# sunclock.net
KiCad netlist of a schematic drawn in EAGLE
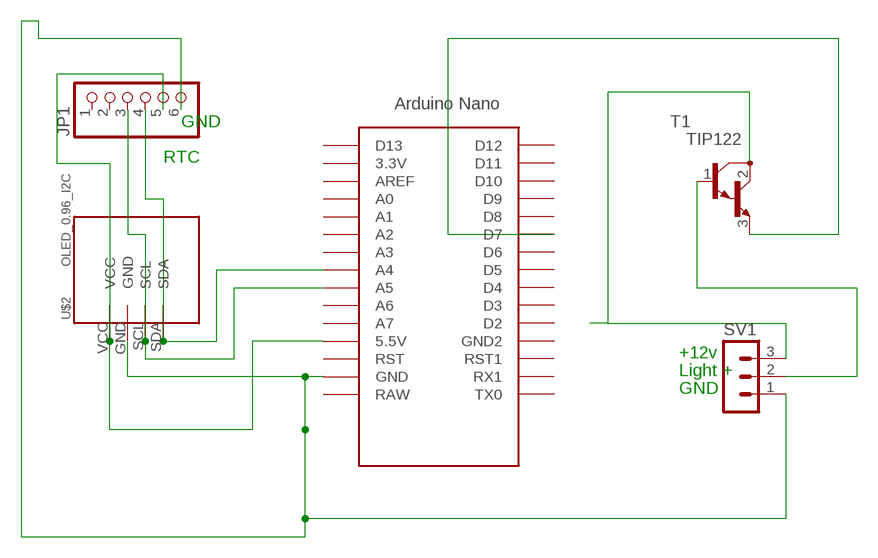
[diagram p0: schematic, sheet 1]

(export (version "E")
  (design (tool "Eeschema 10.0.6"))
  (components
    (comp (ref "JP1")
      (value "PINHD-1X6")
      (footprint "eagle-import:1X06")
      (libsource (lib "eagle-import") (part "PINHD-1X6"))
    )
    (comp (ref "SV1")
      (value "MA03-1")
      (footprint "eagle-import:MA03-1")
      (libsource (lib "eagle-import") (part "MA03-1"))
    )
    (comp (ref "T1")
      (value "TIP122")
      (footprint "eagle-import:TO220")
      (fields (field (name "MF") "ON Semiconductor"))
      (libsource (lib "eagle-import") (part "TIP122"))
    )
    (comp (ref "U$1")
      (value "NANO")
      (footprint "eagle-import:NANO")
      (libsource (lib "eagle-import") (part "NANO"))
    )
    (comp (ref "U$2")
      (value "OLED_0.96_I2C")
      (footprint "eagle-import:OLED_0.96_I2C")
      (libsource (lib "eagle-import") (part "OLED_0.96_I2C"))
    )
  )
  (nets
    (net (code "1") (name "Net-(JP1-Pad3)") (class "Default")
      (node (ref "JP1") (pin "3") (pinfunction "3_3") (pintype "passive"))
      (node (ref "U$1") (pin "A5") (pinfunction "A5_A5") (pintype "bidirectional"))
      (node (ref "U$2") (pin "SCL") (pinfunction "SCL_SCL") (pintype "bidirectional"))
    )
    (net (code "2") (name "Net-(JP1-Pad4)") (class "Default")
      (node (ref "JP1") (pin "4") (pinfunction "4_4") (pintype "passive"))
      (node (ref "U$1") (pin "A4") (pinfunction "A4_A4") (pintype "bidirectional"))
      (node (ref "U$2") (pin "SDA") (pinfunction "SDA_SDA") (pintype "bidirectional"))
    )
    (net (code "3") (name "Net-(JP1-Pad6)") (class "Default")
      (node (ref "JP1") (pin "6") (pinfunction "6_6") (pintype "passive"))
      (node (ref "SV1") (pin "1") (pinfunction "1_1") (pintype "passive"))
      (node (ref "U$1") (pin "GND") (pinfunction "GND_GND") (pintype "bidirectional"))
      (node (ref "U$2") (pin "GND") (pinfunction "GND_GND") (pintype "bidirectional"))
    )
    (net (code "4") (name "Net-(T1-B)") (class "Default")
      (node (ref "SV1") (pin "2") (pinfunction "2_2") (pintype "passive"))
      (node (ref "T1") (pin "1") (pinfunction "B_1") (pintype "passive"))
    )
    (net (code "5") (name "Net-(T1-C)") (class "Default")
      (node (ref "SV1") (pin "3") (pinfunction "3_3") (pintype "passive"))
      (node (ref "T1") (pin "2") (pinfunction "C_2") (pintype "passive"))
    )
    (net (code "6") (name "Net-(T1-E)") (class "Default")
      (node (ref "T1") (pin "3") (pinfunction "E_3") (pintype "passive"))
      (node (ref "U$1") (pin "D7") (pinfunction "D7_D7") (pintype "bidirectional"))
    )
    (net (code "7") (name "Net-(U$1-5.5V)") (class "Default")
      (node (ref "JP1") (pin "5") (pinfunction "5_5") (pintype "passive"))
      (node (ref "U$1") (pin "5V") (pinfunction "5.5V_5V") (pintype "bidirectional"))
      (node (ref "U$2") (pin "VCC") (pinfunction "VCC_VCC") (pintype "bidirectional"))
    )
    (net (code "8") (name "unconnected-(JP1-Pad1)") (class "Default")
      (node (ref "JP1") (pin "1") (pinfunction "1_1") (pintype "passive"))
    )
    (net (code "9") (name "unconnected-(JP1-Pad2)") (class "Default")
      (node (ref "JP1") (pin "2") (pinfunction "2_2") (pintype "passive"))
    )
    (net (code "10") (name "unconnected-(U$1-GND2-PadGND1)") (class "Default")
      (node (ref "U$1") (pin "GND1") (pinfunction "GND2_GND1") (pintype "bidirectional"))
    )
    (net (code "11") (name "unconnected-(U$1-Pad3.3V)") (class "Default")
      (node (ref "U$1") (pin "3.3V") (pinfunction "3.3V_3.3V") (pintype "bidirectional"))
    )
    (net (code "12") (name "unconnected-(U$1-PadA0)") (class "Default")
      (node (ref "U$1") (pin "A0") (pinfunction "A0_A0") (pintype "bidirectional"))
    )
    (net (code "13") (name "unconnected-(U$1-PadA1)") (class "Default")
      (node (ref "U$1") (pin "A1") (pinfunction "A1_A1") (pintype "bidirectional"))
    )
    (net (code "14") (name "unconnected-(U$1-PadA2)") (class "Default")
      (node (ref "U$1") (pin "A2") (pinfunction "A2_A2") (pintype "bidirectional"))
    )
    (net (code "15") (name "unconnected-(U$1-PadA3)") (class "Default")
      (node (ref "U$1") (pin "A3") (pinfunction "A3_A3") (pintype "bidirectional"))
    )
    (net (code "16") (name "unconnected-(U$1-PadA6)") (class "Default")
      (node (ref "U$1") (pin "A6") (pinfunction "A6_A6") (pintype "bidirectional"))
    )
    (net (code "17") (name "unconnected-(U$1-PadA7)") (class "Default")
      (node (ref "U$1") (pin "A7") (pinfunction "A7_A7") (pintype "bidirectional"))
    )
    (net (code "18") (name "unconnected-(U$1-PadAREF)") (class "Default")
      (node (ref "U$1") (pin "AREF") (pinfunction "AREF_AREF") (pintype "bidirectional"))
    )
    (net (code "19") (name "unconnected-(U$1-PadD2)") (class "Default")
      (node (ref "U$1") (pin "D2") (pinfunction "D2_D2") (pintype "bidirectional"))
    )
    (net (code "20") (name "unconnected-(U$1-PadD3)") (class "Default")
      (node (ref "U$1") (pin "D3") (pinfunction "D3_D3") (pintype "bidirectional"))
    )
    (net (code "21") (name "unconnected-(U$1-PadD4)") (class "Default")
      (node (ref "U$1") (pin "D4") (pinfunction "D4_D4") (pintype "bidirectional"))
    )
    (net (code "22") (name "unconnected-(U$1-PadD5)") (class "Default")
      (node (ref "U$1") (pin "D5") (pinfunction "D5_D5") (pintype "bidirectional"))
    )
    (net (code "23") (name "unconnected-(U$1-PadD6)") (class "Default")
      (node (ref "U$1") (pin "D6") (pinfunction "D6_D6") (pintype "bidirectional"))
    )
    (net (code "24") (name "unconnected-(U$1-PadD8)") (class "Default")
      (node (ref "U$1") (pin "D8") (pinfunction "D8_D8") (pintype "bidirectional"))
    )
    (net (code "25") (name "unconnected-(U$1-PadD9)") (class "Default")
      (node (ref "U$1") (pin "D9") (pinfunction "D9_D9") (pintype "bidirectional"))
    )
    (net (code "26") (name "unconnected-(U$1-PadD10)") (class "Default")
      (node (ref "U$1") (pin "D10") (pinfunction "D10_D10") (pintype "bidirectional"))
    )
    (net (code "27") (name "unconnected-(U$1-PadD11)") (class "Default")
      (node (ref "U$1") (pin "D11") (pinfunction "D11_D11") (pintype "bidirectional"))
    )
    (net (code "28") (name "unconnected-(U$1-PadD12)") (class "Default")
      (node (ref "U$1") (pin "D12") (pinfunction "D12_D12") (pintype "bidirectional"))
    )
    (net (code "29") (name "unconnected-(U$1-PadD13)") (class "Default")
      (node (ref "U$1") (pin "D13") (pinfunction "D13_D13") (pintype "bidirectional"))
    )
    (net (code "30") (name "unconnected-(U$1-PadICSP1)") (class "Default")
      (node (ref "U$1") (pin "ICSP1") (pinfunction "ICSP1_ICSP1") (pintype "bidirectional"))
    )
    (net (code "31") (name "unconnected-(U$1-PadICSP2)") (class "Default")
      (node (ref "U$1") (pin "ICSP2") (pinfunction "ICSP2_ICSP2") (pintype "bidirectional"))
    )
    (net (code "32") (name "unconnected-(U$1-PadICSP3)") (class "Default")
      (node (ref "U$1") (pin "ICSP3") (pinfunction "ICSP3_ICSP3") (pintype "bidirectional"))
    )
    (net (code "33") (name "unconnected-(U$1-PadICSP4)") (class "Default")
      (node (ref "U$1") (pin "ICSP4") (pinfunction "ICSP4_ICSP4") (pintype "bidirectional"))
    )
    (net (code "34") (name "unconnected-(U$1-PadICSP5)") (class "Default")
      (node (ref "U$1") (pin "ICSP5") (pinfunction "ICSP5_ICSP5") (pintype "bidirectional"))
    )
    (net (code "35") (name "unconnected-(U$1-PadICSP6)") (class "Default")
      (node (ref "U$1") (pin "ICSP6") (pinfunction "ICSP6_ICSP6") (pintype "bidirectional"))
    )
    (net (code "36") (name "unconnected-(U$1-PadRAW)") (class "Default")
      (node (ref "U$1") (pin "RAW") (pinfunction "RAW_RAW") (pintype "bidirectional"))
    )
    (net (code "37") (name "unconnected-(U$1-PadRST)") (class "Default")
      (node (ref "U$1") (pin "RST") (pinfunction "RST_RST") (pintype "bidirectional"))
    )
    (net (code "38") (name "unconnected-(U$1-PadRST1)") (class "Default")
      (node (ref "U$1") (pin "RST1") (pinfunction "RST1_RST1") (pintype "bidirectional"))
    )
    (net (code "39") (name "unconnected-(U$1-PadRX1)") (class "Default")
      (node (ref "U$1") (pin "RX1") (pinfunction "RX1_RX1") (pintype "bidirectional"))
    )
    (net (code "40") (name "unconnected-(U$1-PadTX0)") (class "Default")
      (node (ref "U$1") (pin "TX0") (pinfunction "TX0_TX0") (pintype "bidirectional"))
    )
  )
)
